# Sheet1_2518_MEZ.net
KiCad netlist of a schematic drawn in Altium Designer
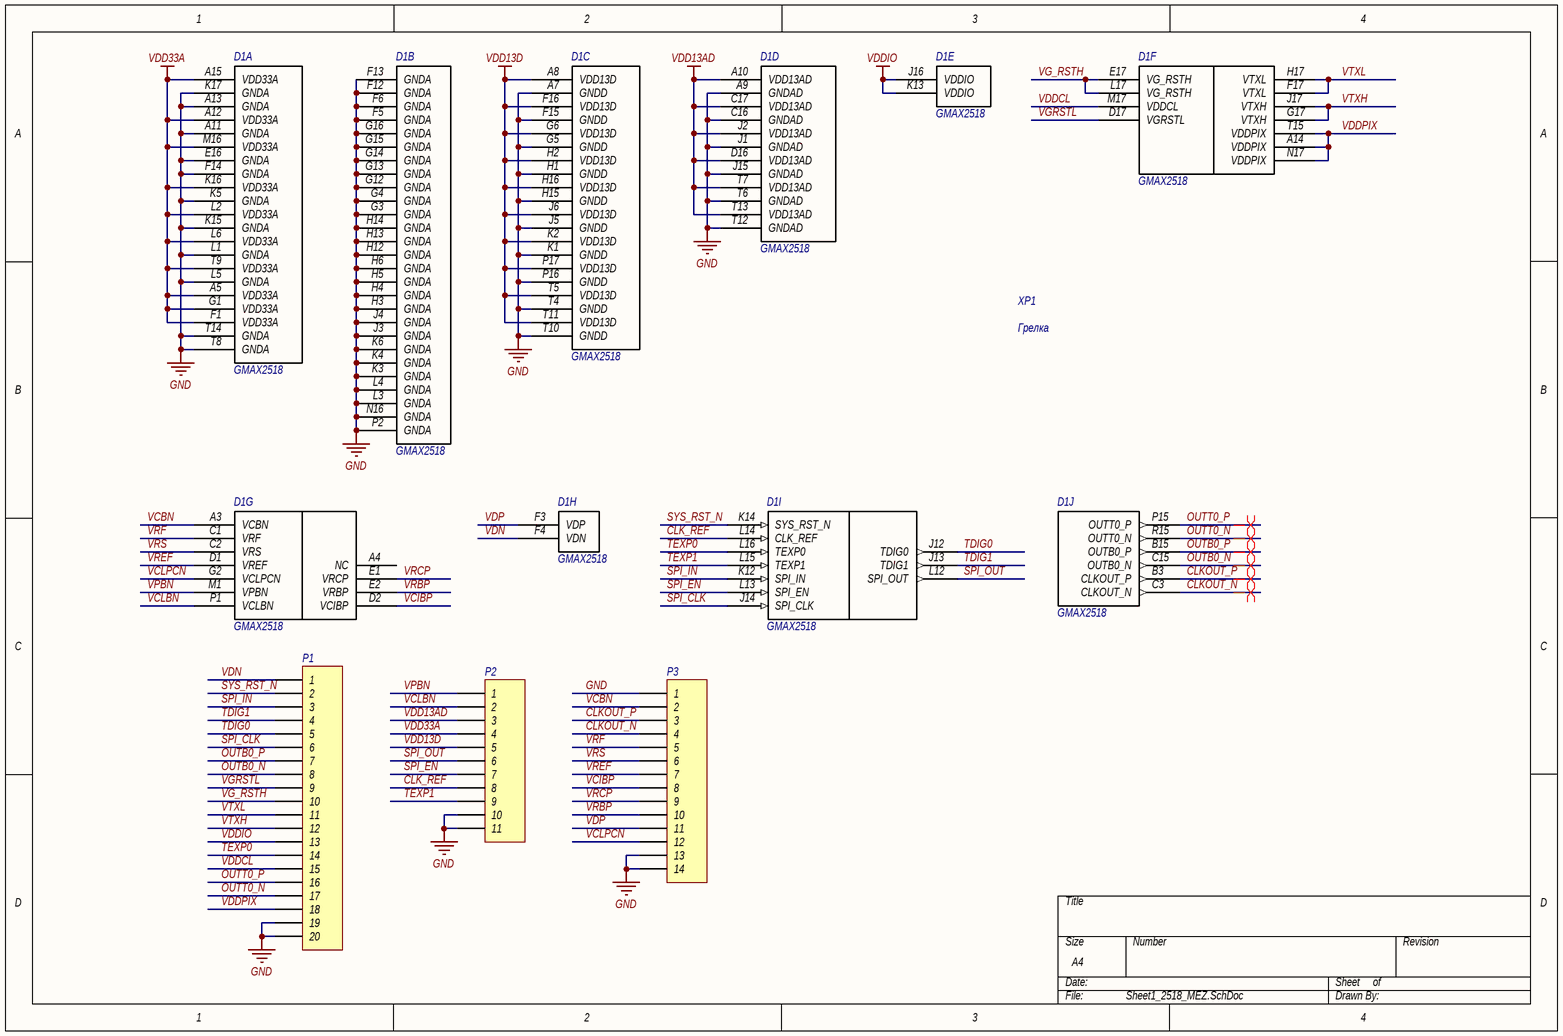
[diagram p0: Sheet1_2518_MEZ.SchDoc]

(export (version "E")
  (design (tool "Eeschema 10.0.6"))
  (components
    (comp (ref "D1") (value "GMAX2518") (footprint "GMAX2518") (libsource (lib "Schlib") (part "GMAX2518")))
    (comp (ref "P1")
      (value "Header 20")
      (footprint "HDR1X20")
      (description "Header, 20-Pin")
      (fields (field (name "PUBLISHER") "Altium Limited"))
      (libsource (lib "Miscellaneous Connectors") (part "Header 20"))
    )
    (comp (ref "P2")
      (value "Header 11")
      (footprint "HDR1X11")
      (description "Header, 11-Pin")
      (fields (field (name "PUBLISHER") "Altium Limited"))
      (libsource (lib "Miscellaneous Connectors") (part "Header 11"))
    )
    (comp (ref "P3")
      (value "Header 14")
      (footprint "HDR1X14")
      (description "Header, 14-Pin")
      (fields (field (name "PUBLISHER") "Altium Limited"))
      (libsource (lib "Miscellaneous Connectors") (part "Header 14"))
    )
    (comp (ref "XP1") (value "Грелка") (footprint "Грелка") (libsource (lib "VPL") (part "Грелка")))
  )
  (nets
    (net (code "1") (name "/CLKOUT_N") (class "Default")
      (node (ref "D1") (pin "C3") (pinfunction "CLKOUT_N_C3") (pintype "output"))
      (node (ref "P3") (pin "4") (pinfunction "4_4") (pintype "passive"))
    )
    (net (code "2") (name "/CLKOUT_P") (class "Default")
      (node (ref "D1") (pin "B3") (pinfunction "CLKOUT_P_B3") (pintype "output"))
      (node (ref "P3") (pin "3") (pinfunction "3_3") (pintype "passive"))
    )
    (net (code "3") (name "/CLK_REF") (class "Default")
      (node (ref "D1") (pin "L14") (pinfunction "CLK_REF_L14") (pintype "input"))
      (node (ref "P2") (pin "8") (pinfunction "8_8") (pintype "passive"))
    )
    (net (code "4") (name "/OUTB0_N") (class "Default")
      (node (ref "D1") (pin "C15") (pinfunction "OUTB0_N_C15") (pintype "output"))
      (node (ref "P1") (pin "8") (pinfunction "8_8") (pintype "passive"))
    )
    (net (code "5") (name "/OUTB0_P") (class "Default")
      (node (ref "D1") (pin "B15") (pinfunction "OUTB0_P_B15") (pintype "output"))
      (node (ref "P1") (pin "7") (pinfunction "7_7") (pintype "passive"))
    )
    (net (code "6") (name "/OUTT0_N") (class "Default")
      (node (ref "D1") (pin "R15") (pinfunction "OUTT0_N_R15") (pintype "output"))
      (node (ref "P1") (pin "17") (pinfunction "17_17") (pintype "passive"))
    )
    (net (code "7") (name "/OUTT0_P") (class "Default")
      (node (ref "D1") (pin "P15") (pinfunction "OUTT0_P_P15") (pintype "output"))
      (node (ref "P1") (pin "16") (pinfunction "16_16") (pintype "passive"))
    )
    (net (code "8") (name "/SPI_CLK") (class "Default")
      (node (ref "D1") (pin "J14") (pinfunction "SPI_CLK_J14") (pintype "input"))
      (node (ref "P1") (pin "6") (pinfunction "6_6") (pintype "passive"))
    )
    (net (code "9") (name "/SPI_EN") (class "Default")
      (node (ref "D1") (pin "L13") (pinfunction "SPI_EN_L13") (pintype "input"))
      (node (ref "P2") (pin "7") (pinfunction "7_7") (pintype "passive"))
    )
    (net (code "10") (name "/SPI_IN") (class "Default")
      (node (ref "D1") (pin "K12") (pinfunction "SPI_IN_K12") (pintype "input"))
      (node (ref "P1") (pin "3") (pinfunction "3_3") (pintype "passive"))
    )
    (net (code "11") (name "/SPI_OUT") (class "Default")
      (node (ref "D1") (pin "L12") (pinfunction "SPI_OUT_L12") (pintype "output"))
      (node (ref "P2") (pin "6") (pinfunction "6_6") (pintype "passive"))
    )
    (net (code "12") (name "/SYS_RST_N") (class "Default")
      (node (ref "D1") (pin "K14") (pinfunction "SYS_RST_N_K14") (pintype "input"))
      (node (ref "P1") (pin "2") (pinfunction "2_2") (pintype "passive"))
    )
    (net (code "13") (name "/TDIG0") (class "Default")
      (node (ref "D1") (pin "J12") (pinfunction "TDIG0_J12") (pintype "output"))
      (node (ref "P1") (pin "5") (pinfunction "5_5") (pintype "passive"))
    )
    (net (code "14") (name "/TDIG1") (class "Default")
      (node (ref "D1") (pin "J13") (pinfunction "TDIG1_J13") (pintype "output"))
      (node (ref "P1") (pin "4") (pinfunction "4_4") (pintype "passive"))
    )
    (net (code "15") (name "/TEXP0") (class "Default")
      (node (ref "D1") (pin "L16") (pinfunction "TEXP0_L16") (pintype "input"))
      (node (ref "P1") (pin "14") (pinfunction "14_14") (pintype "passive"))
    )
    (net (code "16") (name "/TEXP1") (class "Default")
      (node (ref "D1") (pin "L15") (pinfunction "TEXP1_L15") (pintype "input"))
      (node (ref "P2") (pin "9") (pinfunction "9_9") (pintype "passive"))
    )
    (net (code "17") (name "/VCBN") (class "Default")
      (node (ref "D1") (pin "A3") (pinfunction "VCBN_A3") (pintype "passive"))
      (node (ref "P3") (pin "2") (pinfunction "2_2") (pintype "passive"))
    )
    (net (code "18") (name "/VCIBP") (class "Default")
      (node (ref "D1") (pin "D2") (pinfunction "VCIBP_D2") (pintype "passive"))
      (node (ref "P3") (pin "8") (pinfunction "8_8") (pintype "passive"))
    )
    (net (code "19") (name "/VCLBN") (class "Default")
      (node (ref "D1") (pin "P1") (pinfunction "VCLBN_P1") (pintype "passive"))
      (node (ref "P2") (pin "2") (pinfunction "2_2") (pintype "passive"))
    )
    (net (code "20") (name "/VCLPCN") (class "Default")
      (node (ref "D1") (pin "G2") (pinfunction "VCLPCN_G2") (pintype "passive"))
      (node (ref "P3") (pin "12") (pinfunction "12_12") (pintype "passive"))
    )
    (net (code "21") (name "/VDDCL") (class "Default")
      (node (ref "D1") (pin "M17") (pinfunction "VDDCL_M17") (pintype "passive"))
      (node (ref "P1") (pin "15") (pinfunction "15_15") (pintype "passive"))
    )
    (net (code "22") (name "/VDDPIX") (class "Default")
      (node (ref "D1") (pin "A14") (pinfunction "VDDPIX_A14") (pintype "passive"))
      (node (ref "D1") (pin "N17") (pinfunction "VDDPIX_N17") (pintype "passive"))
      (node (ref "D1") (pin "T15") (pinfunction "VDDPIX_T15") (pintype "passive"))
      (node (ref "P1") (pin "18") (pinfunction "18_18") (pintype "passive"))
    )
    (net (code "23") (name "/VDN") (class "Default")
      (node (ref "D1") (pin "F4") (pinfunction "VDN_F4") (pintype "passive"))
      (node (ref "P1") (pin "1") (pinfunction "1_1") (pintype "passive"))
    )
    (net (code "24") (name "/VDP") (class "Default")
      (node (ref "D1") (pin "F3") (pinfunction "VDP_F3") (pintype "passive"))
      (node (ref "P3") (pin "11") (pinfunction "11_11") (pintype "passive"))
    )
    (net (code "25") (name "/VGRSTL") (class "Default")
      (node (ref "D1") (pin "D17") (pinfunction "VGRSTL_D17") (pintype "passive"))
      (node (ref "P1") (pin "9") (pinfunction "9_9") (pintype "passive"))
    )
    (net (code "26") (name "/VG_RSTH") (class "Default")
      (node (ref "D1") (pin "E17") (pinfunction "VG_RSTH_E17") (pintype "passive"))
      (node (ref "D1") (pin "L17") (pinfunction "VG_RSTH_L17") (pintype "passive"))
      (node (ref "P1") (pin "10") (pinfunction "10_10") (pintype "passive"))
    )
    (net (code "27") (name "/VPBN") (class "Default")
      (node (ref "D1") (pin "M1") (pinfunction "VPBN_M1") (pintype "passive"))
      (node (ref "P2") (pin "1") (pinfunction "1_1") (pintype "passive"))
    )
    (net (code "28") (name "/VRBP") (class "Default")
      (node (ref "D1") (pin "E2") (pinfunction "VRBP_E2") (pintype "passive"))
      (node (ref "P3") (pin "10") (pinfunction "10_10") (pintype "passive"))
    )
    (net (code "29") (name "/VRCP") (class "Default")
      (node (ref "D1") (pin "E1") (pinfunction "VRCP_E1") (pintype "passive"))
      (node (ref "P3") (pin "9") (pinfunction "9_9") (pintype "passive"))
    )
    (net (code "30") (name "/VREF") (class "Default")
      (node (ref "D1") (pin "D1") (pinfunction "VREF_D1") (pintype "passive"))
      (node (ref "P3") (pin "7") (pinfunction "7_7") (pintype "passive"))
    )
    (net (code "31") (name "/VRF") (class "Default")
      (node (ref "D1") (pin "C1") (pinfunction "VRF_C1") (pintype "passive"))
      (node (ref "P3") (pin "5") (pinfunction "5_5") (pintype "passive"))
    )
    (net (code "32") (name "/VRS") (class "Default")
      (node (ref "D1") (pin "C2") (pinfunction "VRS_C2") (pintype "passive"))
      (node (ref "P3") (pin "6") (pinfunction "6_6") (pintype "passive"))
    )
    (net (code "33") (name "/VTXH") (class "Default")
      (node (ref "D1") (pin "G17") (pinfunction "VTXH_G17") (pintype "passive"))
      (node (ref "D1") (pin "J17") (pinfunction "VTXH_J17") (pintype "passive"))
      (node (ref "P1") (pin "12") (pinfunction "12_12") (pintype "passive"))
    )
    (net (code "34") (name "/VTXL") (class "Default")
      (node (ref "D1") (pin "F17") (pinfunction "VTXL_F17") (pintype "passive"))
      (node (ref "D1") (pin "H17") (pinfunction "VTXL_H17") (pintype "passive"))
      (node (ref "P1") (pin "11") (pinfunction "11_11") (pintype "passive"))
    )
    (net (code "35") (name "GND") (class "Default")
      (node (ref "D1") (pin "A11") (pinfunction "GNDA_A11") (pintype "passive"))
      (node (ref "D1") (pin "A13") (pinfunction "GNDA_A13") (pintype "passive"))
      (node (ref "D1") (pin "A7") (pinfunction "GNDD_A7") (pintype "passive"))
      (node (ref "D1") (pin "A9") (pinfunction "GNDAD_A9") (pintype "passive"))
      (node (ref "D1") (pin "C16") (pinfunction "GNDAD_C16") (pintype "passive"))
      (node (ref "D1") (pin "E16") (pinfunction "GNDA_E16") (pintype "passive"))
      (node (ref "D1") (pin "F12") (pinfunction "GNDA_F12") (pintype "passive"))
      (node (ref "D1") (pin "F13") (pinfunction "GNDA_F13") (pintype "passive"))
      (node (ref "D1") (pin "F14") (pinfunction "GNDA_F14") (pintype "passive"))
      (node (ref "D1") (pin "F15") (pinfunction "GNDD_F15") (pintype "passive"))
      (node (ref "D1") (pin "F5") (pinfunction "GNDA_F5") (pintype "passive"))
      (node (ref "D1") (pin "F6") (pinfunction "GNDA_F6") (pintype "passive"))
      (node (ref "D1") (pin "G12") (pinfunction "GNDA_G12") (pintype "passive"))
      (node (ref "D1") (pin "G13") (pinfunction "GNDA_G13") (pintype "passive"))
      (node (ref "D1") (pin "G14") (pinfunction "GNDA_G14") (pintype "passive"))
      (node (ref "D1") (pin "G15") (pinfunction "GNDA_G15") (pintype "passive"))
      (node (ref "D1") (pin "G16") (pinfunction "GNDA_G16") (pintype "passive"))
      (node (ref "D1") (pin "G3") (pinfunction "GNDA_G3") (pintype "passive"))
      (node (ref "D1") (pin "G4") (pinfunction "GNDA_G4") (pintype "passive"))
      (node (ref "D1") (pin "G5") (pinfunction "GNDD_G5") (pintype "passive"))
      (node (ref "D1") (pin "H1") (pinfunction "GNDD_H1") (pintype "passive"))
      (node (ref "D1") (pin "H12") (pinfunction "GNDA_H12") (pintype "passive"))
      (node (ref "D1") (pin "H13") (pinfunction "GNDA_H13") (pintype "passive"))
      (node (ref "D1") (pin "H14") (pinfunction "GNDA_H14") (pintype "passive"))
      (node (ref "D1") (pin "H15") (pinfunction "GNDD_H15") (pintype "passive"))
      (node (ref "D1") (pin "H3") (pinfunction "GNDA_H3") (pintype "passive"))
      (node (ref "D1") (pin "H4") (pinfunction "GNDA_H4") (pintype "passive"))
      (node (ref "D1") (pin "H5") (pinfunction "GNDA_H5") (pintype "passive"))
      (node (ref "D1") (pin "H6") (pinfunction "GNDA_H6") (pintype "passive"))
      (node (ref "D1") (pin "J1") (pinfunction "GNDAD_J1") (pintype "passive"))
      (node (ref "D1") (pin "J15") (pinfunction "GNDAD_J15") (pintype "passive"))
      (node (ref "D1") (pin "J3") (pinfunction "GNDA_J3") (pintype "passive"))
      (node (ref "D1") (pin "J4") (pinfunction "GNDA_J4") (pintype "passive"))
      (node (ref "D1") (pin "J5") (pinfunction "GNDD_J5") (pintype "passive"))
      (node (ref "D1") (pin "K1") (pinfunction "GNDD_K1") (pintype "passive"))
      (node (ref "D1") (pin "K15") (pinfunction "GNDA_K15") (pintype "passive"))
      (node (ref "D1") (pin "K17") (pinfunction "GNDA_K17") (pintype "passive"))
      (node (ref "D1") (pin "K3") (pinfunction "GNDA_K3") (pintype "passive"))
      (node (ref "D1") (pin "K4") (pinfunction "GNDA_K4") (pintype "passive"))
      (node (ref "D1") (pin "K5") (pinfunction "GNDA_K5") (pintype "passive"))
      (node (ref "D1") (pin "K6") (pinfunction "GNDA_K6") (pintype "passive"))
      (node (ref "D1") (pin "L1") (pinfunction "GNDA_L1") (pintype "passive"))
      (node (ref "D1") (pin "L3") (pinfunction "GNDA_L3") (pintype "passive"))
      (node (ref "D1") (pin "L4") (pinfunction "GNDA_L4") (pintype "passive"))
      (node (ref "D1") (pin "L5") (pinfunction "GNDA_L5") (pintype "passive"))
      (node (ref "D1") (pin "N16") (pinfunction "GNDA_N16") (pintype "passive"))
      (node (ref "D1") (pin "P16") (pinfunction "GNDD_P16") (pintype "passive"))
      (node (ref "D1") (pin "P2") (pinfunction "GNDA_P2") (pintype "passive"))
      (node (ref "D1") (pin "T10") (pinfunction "GNDD_T10") (pintype "passive"))
      (node (ref "D1") (pin "T12") (pinfunction "GNDAD_T12") (pintype "passive"))
      (node (ref "D1") (pin "T14") (pinfunction "GNDA_T14") (pintype "passive"))
      (node (ref "D1") (pin "T4") (pinfunction "GNDD_T4") (pintype "passive"))
      (node (ref "D1") (pin "T6") (pinfunction "GNDAD_T6") (pintype "passive"))
      (node (ref "D1") (pin "T8") (pinfunction "GNDA_T8") (pintype "passive"))
      (node (ref "P1") (pin "19") (pinfunction "19_19") (pintype "passive"))
      (node (ref "P1") (pin "20") (pinfunction "20_20") (pintype "passive"))
      (node (ref "P2") (pin "10") (pinfunction "10_10") (pintype "passive"))
      (node (ref "P2") (pin "11") (pinfunction "11_11") (pintype "passive"))
      (node (ref "P3") (pin "1") (pinfunction "1_1") (pintype "passive"))
      (node (ref "P3") (pin "13") (pinfunction "13_13") (pintype "passive"))
      (node (ref "P3") (pin "14") (pinfunction "14_14") (pintype "passive"))
    )
    (net (code "36") (name "VDD13AD") (class "Default")
      (node (ref "D1") (pin "A10") (pinfunction "VDD13AD_A10") (pintype "passive"))
      (node (ref "D1") (pin "C17") (pinfunction "VDD13AD_C17") (pintype "passive"))
      (node (ref "D1") (pin "D16") (pinfunction "VDD13AD_D16") (pintype "passive"))
      (node (ref "D1") (pin "J2") (pinfunction "VDD13AD_J2") (pintype "passive"))
      (node (ref "D1") (pin "T13") (pinfunction "VDD13AD_T13") (pintype "passive"))
      (node (ref "D1") (pin "T7") (pinfunction "VDD13AD_T7") (pintype "passive"))
      (node (ref "P2") (pin "3") (pinfunction "3_3") (pintype "passive"))
    )
    (net (code "37") (name "VDD13D") (class "Default")
      (node (ref "D1") (pin "A8") (pinfunction "VDD13D_A8") (pintype "passive"))
      (node (ref "D1") (pin "F16") (pinfunction "VDD13D_F16") (pintype "passive"))
      (node (ref "D1") (pin "G6") (pinfunction "VDD13D_G6") (pintype "passive"))
      (node (ref "D1") (pin "H16") (pinfunction "VDD13D_H16") (pintype "passive"))
      (node (ref "D1") (pin "H2") (pinfunction "VDD13D_H2") (pintype "passive"))
      (node (ref "D1") (pin "J6") (pinfunction "VDD13D_J6") (pintype "passive"))
      (node (ref "D1") (pin "K2") (pinfunction "VDD13D_K2") (pintype "passive"))
      (node (ref "D1") (pin "P17") (pinfunction "VDD13D_P17") (pintype "passive"))
      (node (ref "D1") (pin "T11") (pinfunction "VDD13D_T11") (pintype "passive"))
      (node (ref "D1") (pin "T5") (pinfunction "VDD13D_T5") (pintype "passive"))
      (node (ref "P2") (pin "5") (pinfunction "5_5") (pintype "passive"))
    )
    (net (code "38") (name "VDD33A") (class "Default")
      (node (ref "D1") (pin "A12") (pinfunction "VDD33A_A12") (pintype "passive"))
      (node (ref "D1") (pin "A15") (pinfunction "VDD33A_A15") (pintype "passive"))
      (node (ref "D1") (pin "A5") (pinfunction "VDD33A_A5") (pintype "passive"))
      (node (ref "D1") (pin "F1") (pinfunction "VDD33A_F1") (pintype "passive"))
      (node (ref "D1") (pin "G1") (pinfunction "VDD33A_G1") (pintype "passive"))
      (node (ref "D1") (pin "K16") (pinfunction "VDD33A_K16") (pintype "passive"))
      (node (ref "D1") (pin "L2") (pinfunction "VDD33A_L2") (pintype "passive"))
      (node (ref "D1") (pin "L6") (pinfunction "VDD33A_L6") (pintype "passive"))
      (node (ref "D1") (pin "M16") (pinfunction "VDD33A_M16") (pintype "passive"))
      (node (ref "D1") (pin "T9") (pinfunction "VDD33A_T9") (pintype "passive"))
      (node (ref "P2") (pin "4") (pinfunction "4_4") (pintype "passive"))
    )
    (net (code "39") (name "VDDIO") (class "Default")
      (node (ref "D1") (pin "J16") (pinfunction "VDDIO_J16") (pintype "passive"))
      (node (ref "D1") (pin "K13") (pinfunction "VDDIO_K13") (pintype "passive"))
      (node (ref "P1") (pin "13") (pinfunction "13_13") (pintype "passive"))
    )
    (net (code "40") (name "unconnected-(D1G-NC-PadA4)") (class "Default")
      (node (ref "D1") (pin "A4") (pinfunction "NC_A4") (pintype "passive"))
    )
  )
)
